# USB_HS_PHY.net
KiCad netlist of a schematic drawn in Altium Designer
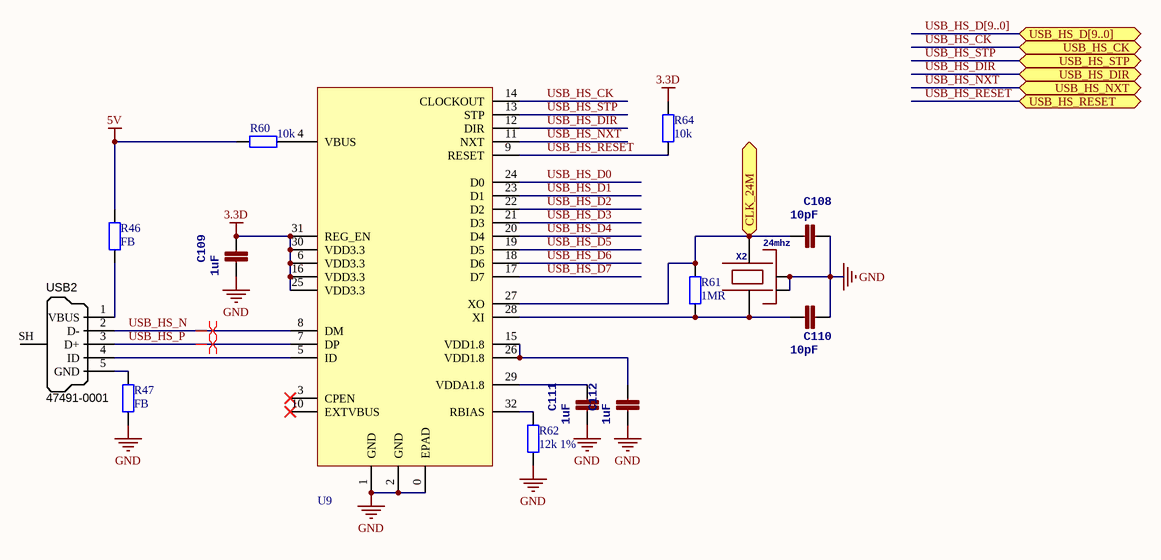
[diagram p0: USB_HS_PHY.SchDoc]

(export (version "E")
  (design (tool "Eeschema 10.0.6"))
  (components
    (comp (ref "C108")
      (value "10pF")
      (footprint "0402")
      (description "<b>Capacitor</b>\nStandard 0603 ceramic capacitor, and 0.1\" leaded capacitor.")
      (fields (field (name "PARTNO") "CC0402ZRY5V7BB104"))
      (libsource (lib "pixhawk2") (part "CAP0402-CAP"))
    )
    (comp (ref "C109")
      (value "1uF")
      (footprint "0402")
      (description "<b>Capacitor</b>\nStandard 0603 ceramic capacitor, and 0.1\" leaded capacitor.")
      (fields (field (name "PARTNO") "CC0402ZRY5V7BB104"))
      (libsource (lib "") (part "CAP0402-CAP_1"))
    )
    (comp (ref "C110")
      (value "10pF")
      (footprint "0402")
      (description "<b>Capacitor</b>\nStandard 0603 ceramic capacitor, and 0.1\" leaded capacitor.")
      (fields (field (name "PARTNO") "CC0402ZRY5V7BB104"))
      (libsource (lib "*") (part "CAP0402-CAP"))
    )
    (comp (ref "C111")
      (value "1uF")
      (footprint "0402")
      (description "<b>Capacitor</b>\nStandard 0603 ceramic capacitor, and 0.1\" leaded capacitor.")
      (fields (field (name "PARTNO") "CC0402ZRY5V7BB104"))
      (libsource (lib "") (part "CAP0402-CAP_1"))
    )
    (comp (ref "C112")
      (value "1uF")
      (footprint "0402")
      (description "<b>Capacitor</b>\nStandard 0603 ceramic capacitor, and 0.1\" leaded capacitor.")
      (fields (field (name "PARTNO") "CC0402ZRY5V7BB104"))
      (libsource (lib "") (part "CAP0402-CAP_1"))
    )
    (comp (ref "R46")
      (value "FB")
      (footprint "0603")
      (description "Resistor")
      (fields (field (name "PUBLISHER") "Altium Limited"))
      (libsource (lib "") (part "Res2_2"))
    )
    (comp (ref "R47")
      (value "FB")
      (footprint "0603")
      (description "Resistor")
      (fields (field (name "PUBLISHER") "Altium Limited"))
      (libsource (lib "") (part "Res2_2"))
    )
    (comp (ref "R60")
      (value "10k")
      (footprint "0402")
      (description "Resistor")
      (fields (field (name "PUBLISHER") "Altium Limited"))
      (libsource (lib "") (part "Res2_1"))
    )
    (comp (ref "R61")
      (value "1MR")
      (footprint "0402")
      (description "Resistor")
      (fields (field (name "PUBLISHER") "Altium Limited"))
      (libsource (lib "Miscellaneous Devices") (part "Res2"))
    )
    (comp (ref "R62")
      (value "12k 1%")
      (footprint "0402")
      (description "Resistor")
      (fields (field (name "PUBLISHER") "Altium Limited"))
      (libsource (lib "Miscellaneous Devices") (part "Res2"))
    )
    (comp (ref "R64")
      (value "10k")
      (footprint "0402")
      (description "Resistor")
      (fields (field (name "PUBLISHER") "Altium Limited"))
      (libsource (lib "Miscellaneous Devices") (part "Res2"))
    )
    (comp (ref "U9") (value "USB3300_1") (footprint "USB3300") (libsource (lib "F4SDR") (part "USB3300_1")))
    (comp (ref "USB2")
      (value "USB Micro Type B")
      (footprint "MICRO-YZX")
      (description "Connector SMD USB Micro Type B middle mount")
      (fields (field (name "MANUFACTURER PART NUMBER 1") "47491-0001"))
      (libsource (lib "PBL - Connectors") (part "USB_Micro_TypeB"))
    )
    (comp (ref "X2")
      (value "24mhz")
      (footprint "OSCILLATOR-3.2X2.5")
      (description "Crystal Oscillator in 3.2x2.5 SMD")
      (libsource (lib "sch") (part "OSCILLATOR-3.2X2.5"))
    )
  )
  (nets
    (net (code "3") (name "/CLK_24M") (class "Default")
      (node (ref "C108") (pin "2") (pinfunction "2_2") (pintype "passive"))
      (node (ref "R61") (pin "2") (pinfunction "2_2") (pintype "passive"))
      (node (ref "U9") (pin "27") (pinfunction "XO_27") (pintype "passive"))
      (node (ref "X2") (pin "3") (pinfunction "3_3") (pintype "passive"))
    )
    (net (code "4") (name "/USB_HS_CK") (class "Default")
      (node (ref "U9") (pin "14") (pinfunction "CLOCKOUT_14") (pintype "passive"))
    )
    (net (code "5") (name "/USB_HS_D0") (class "Default")
      (node (ref "U9") (pin "24") (pinfunction "D0_24") (pintype "passive"))
    )
    (net (code "6") (name "/USB_HS_D1") (class "Default")
      (node (ref "U9") (pin "23") (pinfunction "D1_23") (pintype "passive"))
    )
    (net (code "7") (name "/USB_HS_D2") (class "Default")
      (node (ref "U9") (pin "22") (pinfunction "D2_22") (pintype "passive"))
    )
    (net (code "8") (name "/USB_HS_D3") (class "Default")
      (node (ref "U9") (pin "21") (pinfunction "D3_21") (pintype "passive"))
    )
    (net (code "9") (name "/USB_HS_D4") (class "Default")
      (node (ref "U9") (pin "20") (pinfunction "D4_20") (pintype "passive"))
    )
    (net (code "10") (name "/USB_HS_D5") (class "Default")
      (node (ref "U9") (pin "19") (pinfunction "D5_19") (pintype "passive"))
    )
    (net (code "11") (name "/USB_HS_D6") (class "Default")
      (node (ref "U9") (pin "18") (pinfunction "D6_18") (pintype "passive"))
    )
    (net (code "12") (name "/USB_HS_D7") (class "Default")
      (node (ref "U9") (pin "17") (pinfunction "D7_17") (pintype "passive"))
    )
    (net (code "13") (name "/USB_HS_DIR") (class "Default")
      (node (ref "U9") (pin "12") (pinfunction "DIR_12") (pintype "passive"))
    )
    (net (code "15") (name "/USB_HS_N") (class "Default")
      (node (ref "U9") (pin "8") (pinfunction "DM_8") (pintype "passive"))
      (node (ref "USB2") (pin "2") (pinfunction "D-_2") (pintype "passive"))
    )
    (net (code "16") (name "/USB_HS_NXT") (class "Default")
      (node (ref "U9") (pin "11") (pinfunction "NXT_11") (pintype "passive"))
    )
    (net (code "17") (name "/USB_HS_P") (class "Default")
      (node (ref "U9") (pin "7") (pinfunction "DP_7") (pintype "passive"))
      (node (ref "USB2") (pin "3") (pinfunction "D+_3") (pintype "passive"))
    )
    (net (code "18") (name "/USB_HS_RESET") (class "Default")
      (node (ref "R64") (pin "1") (pinfunction "1_1") (pintype "passive"))
      (node (ref "U9") (pin "9") (pinfunction "RESET_9") (pintype "passive"))
    )
    (net (code "19") (name "/USB_HS_STP") (class "Default")
      (node (ref "U9") (pin "13") (pinfunction "STP_13") (pintype "passive"))
    )
    (net (code "20") (name "3.3D") (class "Default")
      (node (ref "C109") (pin "1") (pinfunction "1_1") (pintype "passive"))
      (node (ref "R64") (pin "2") (pinfunction "2_2") (pintype "passive"))
      (node (ref "U9") (pin "16") (pinfunction "VDD3.3_16") (pintype "passive"))
      (node (ref "U9") (pin "25") (pinfunction "VDD3.3_25") (pintype "passive"))
      (node (ref "U9") (pin "30") (pinfunction "VDD3.3_30") (pintype "passive"))
      (node (ref "U9") (pin "31") (pinfunction "REG_EN_31") (pintype "passive"))
      (node (ref "U9") (pin "6") (pinfunction "VDD3.3_6") (pintype "passive"))
    )
    (net (code "21") (name "5V") (class "Default")
      (node (ref "R46") (pin "1") (pinfunction "1_1") (pintype "passive"))
      (node (ref "R60") (pin "1") (pinfunction "1_1") (pintype "passive"))
    )
    (net (code "22") (name "GND") (class "Default")
      (node (ref "C108") (pin "1") (pinfunction "1_1") (pintype "passive"))
      (node (ref "C109") (pin "2") (pinfunction "2_2") (pintype "passive"))
      (node (ref "C110") (pin "1") (pinfunction "1_1") (pintype "passive"))
      (node (ref "C111") (pin "2") (pinfunction "2_2") (pintype "passive"))
      (node (ref "C112") (pin "2") (pinfunction "2_2") (pintype "passive"))
      (node (ref "R47") (pin "2") (pinfunction "2_2") (pintype "passive"))
      (node (ref "R62") (pin "1") (pinfunction "1_1") (pintype "passive"))
      (node (ref "U9") (pin "0") (pinfunction "EPAD_0") (pintype "passive"))
      (node (ref "U9") (pin "1") (pinfunction "GND_1") (pintype "passive"))
      (node (ref "U9") (pin "2") (pinfunction "GND_2") (pintype "passive"))
      (node (ref "X2") (pin "2") (pinfunction "NC_2_2") (pintype "open_emitter"))
      (node (ref "X2") (pin "4") (pinfunction "NC_4_4") (pintype "open_emitter"))
    )
    (net (code "23") (name "Net-(C112-Pad1)") (class "Default")
      (node (ref "C112") (pin "1") (pinfunction "1_1") (pintype "passive"))
      (node (ref "U9") (pin "15") (pinfunction "VDD1.8_15") (pintype "passive"))
      (node (ref "U9") (pin "26") (pinfunction "VDD1.8_26") (pintype "passive"))
    )
    (net (code "24") (name "Net-(U9-ID)") (class "Default")
      (node (ref "U9") (pin "5") (pinfunction "ID_5") (pintype "passive"))
      (node (ref "USB2") (pin "4") (pinfunction "ID_4") (pintype "passive"))
    )
    (net (code "25") (name "Net-(U9-RBIAS)") (class "Default")
      (node (ref "R62") (pin "2") (pinfunction "2_2") (pintype "passive"))
      (node (ref "U9") (pin "32") (pinfunction "RBIAS_32") (pintype "passive"))
    )
    (net (code "26") (name "Net-(U9-VBUS)") (class "Default")
      (node (ref "R60") (pin "2") (pinfunction "2_2") (pintype "passive"))
      (node (ref "U9") (pin "4") (pinfunction "VBUS_4") (pintype "passive"))
    )
    (net (code "27") (name "Net-(U9-VDDA1.8)") (class "Default")
      (node (ref "C111") (pin "1") (pinfunction "1_1") (pintype "passive"))
      (node (ref "U9") (pin "29") (pinfunction "VDDA1.8_29") (pintype "passive"))
    )
    (net (code "28") (name "Net-(U9-XI)") (class "Default")
      (node (ref "C110") (pin "2") (pinfunction "2_2") (pintype "passive"))
      (node (ref "R61") (pin "1") (pinfunction "1_1") (pintype "passive"))
      (node (ref "U9") (pin "28") (pinfunction "XI_28") (pintype "passive"))
      (node (ref "X2") (pin "1") (pinfunction "1_1") (pintype "passive"))
    )
    (net (code "29") (name "Net-(USB2-GND)") (class "Default")
      (node (ref "R47") (pin "1") (pinfunction "1_1") (pintype "passive"))
      (node (ref "USB2") (pin "5") (pinfunction "GND_5") (pintype "passive"))
    )
    (net (code "30") (name "Net-(USB2-VBUS)") (class "Default")
      (node (ref "R46") (pin "2") (pinfunction "2_2") (pintype "passive"))
      (node (ref "USB2") (pin "1") (pinfunction "VBUS_1") (pintype "passive"))
    )
    (net (code "31") (name "unconnected-(U9-CPEN-Pad3)") (class "Default")
      (node (ref "U9") (pin "3") (pinfunction "CPEN_3") (pintype "passive+no_connect"))
    )
    (net (code "32") (name "unconnected-(U9-EXTVBUS-Pad10)") (class "Default")
      (node (ref "U9") (pin "10") (pinfunction "EXTVBUS_10") (pintype "passive+no_connect"))
    )
    (net (code "33") (name "unconnected-(USB2-Shell-PadSH)") (class "Default")
      (node (ref "USB2") (pin "SH") (pinfunction "Shell_SH") (pintype "passive"))
    )
  )
)
